# CYV15G0403.net
KiCad netlist of a schematic drawn in Altium Designer
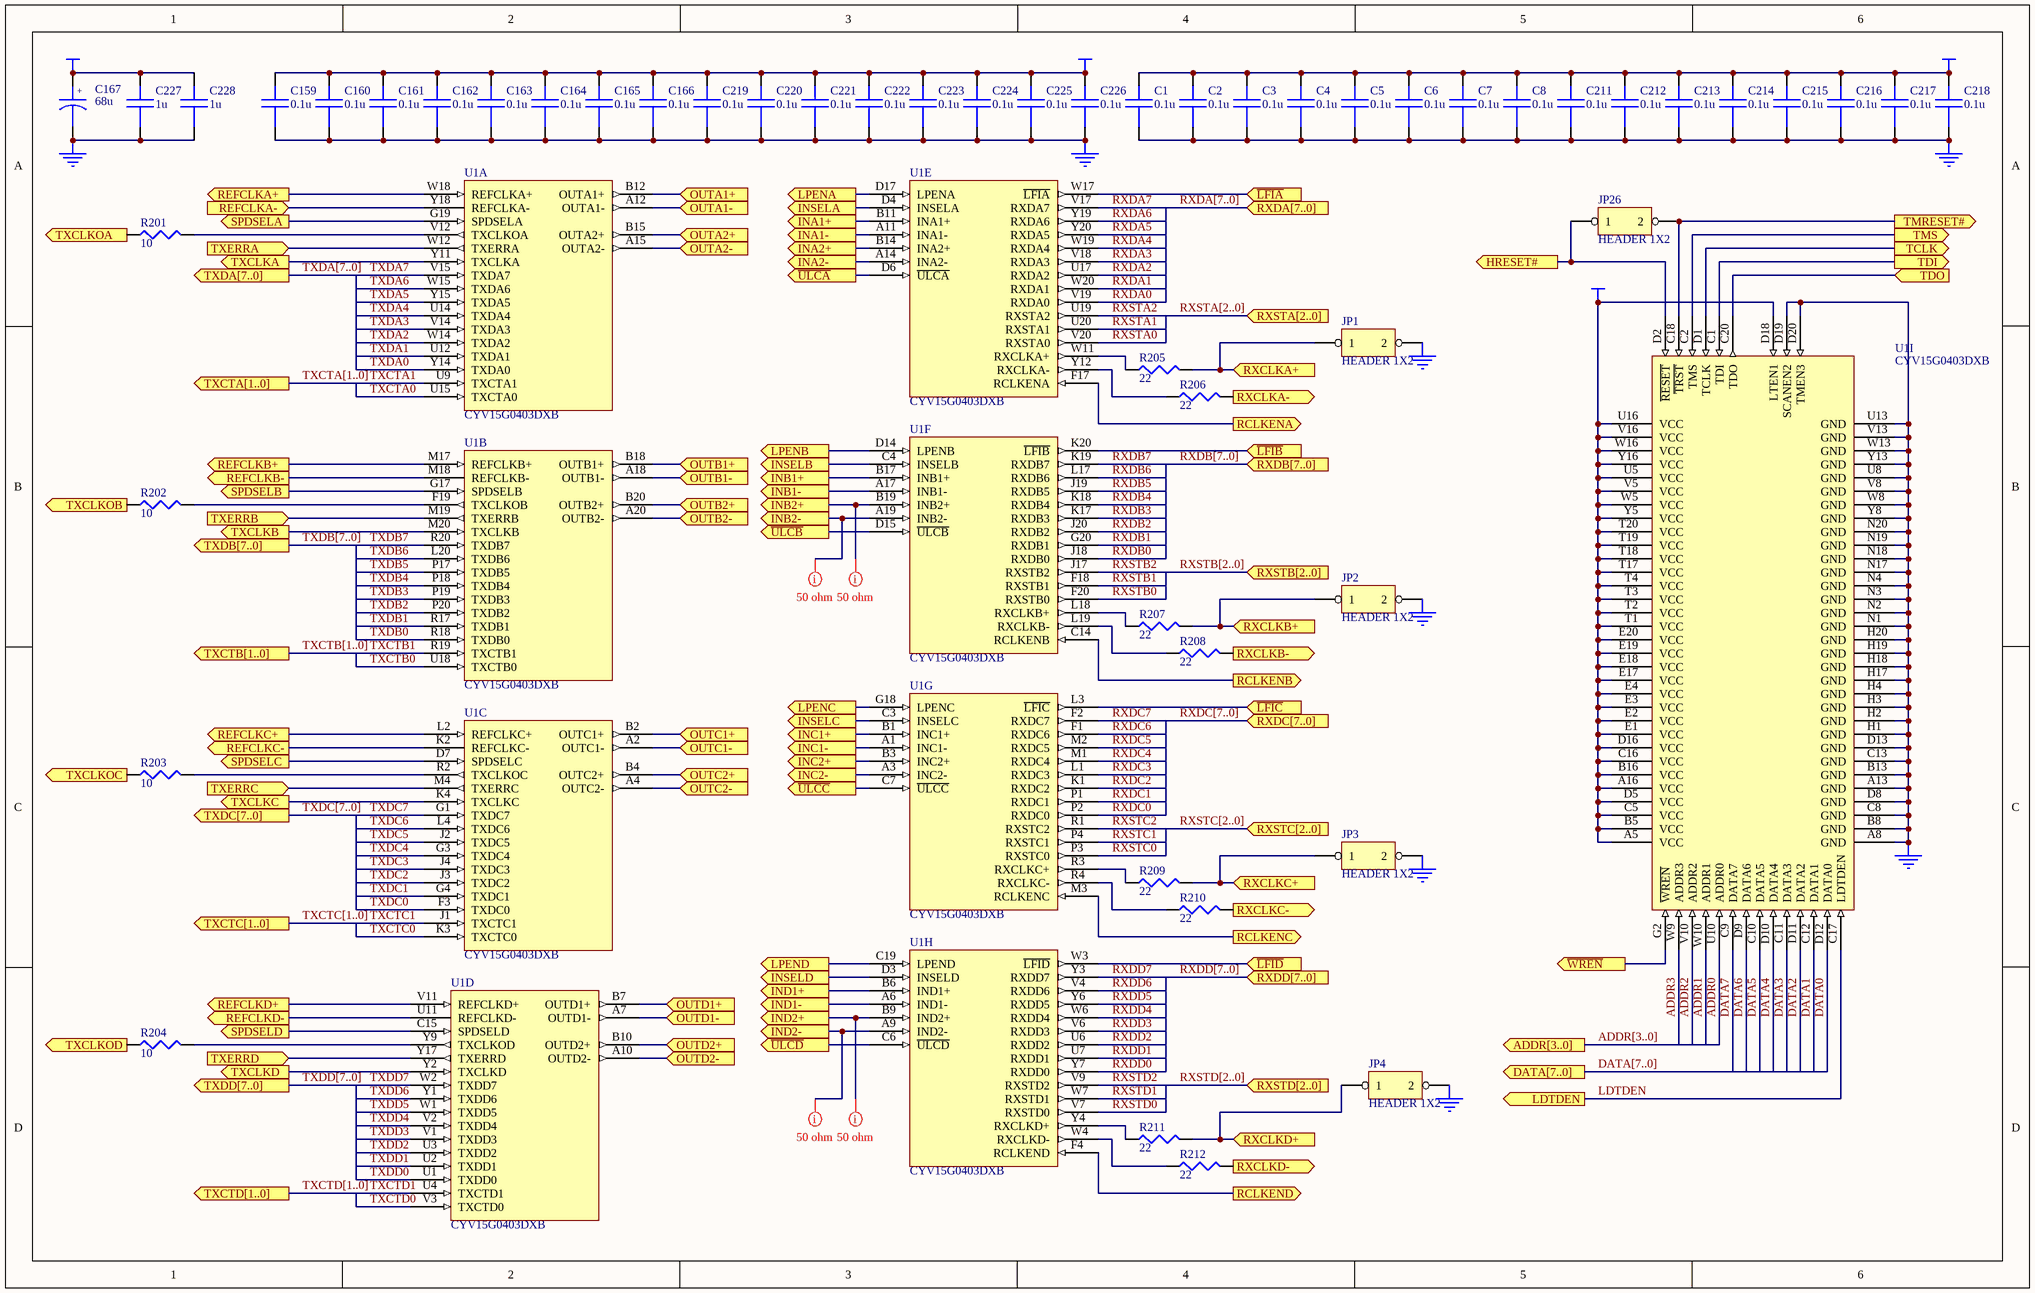
[diagram p0: CYV15G0403.SchDoc]

(export (version "E")
  (design (tool "Eeschema 10.0.6"))
  (components
    (comp (ref "C1")
      (value "~")
      (footprint "0603")
      (description "SMT CAP")
      (libsource (lib "Cypress Molson") (part "CAP"))
    )
    (comp (ref "C2")
      (value "~")
      (footprint "0603")
      (description "SMT CAP")
      (libsource (lib "Cypress Molson") (part "CAP"))
    )
    (comp (ref "C3")
      (value "~")
      (footprint "0603")
      (description "SMT CAP")
      (libsource (lib "Cypress Molson") (part "CAP"))
    )
    (comp (ref "C4")
      (value "~")
      (footprint "0603")
      (description "SMT CAP")
      (libsource (lib "Cypress Molson") (part "CAP"))
    )
    (comp (ref "C5")
      (value "~")
      (footprint "0603")
      (description "SMT CAP")
      (libsource (lib "Cypress Molson") (part "CAP"))
    )
    (comp (ref "C6")
      (value "~")
      (footprint "0603")
      (description "SMT CAP")
      (libsource (lib "Cypress Molson") (part "CAP"))
    )
    (comp (ref "C7")
      (value "~")
      (footprint "0603")
      (description "SMT CAP")
      (libsource (lib "Cypress Molson") (part "CAP"))
    )
    (comp (ref "C8")
      (value "~")
      (footprint "0603")
      (description "SMT CAP")
      (libsource (lib "Cypress Molson") (part "CAP"))
    )
    (comp (ref "C159")
      (value "~")
      (footprint "0603")
      (description "SMT CAP")
      (libsource (lib "Cypress Molson") (part "CAP"))
    )
    (comp (ref "C160")
      (value "~")
      (footprint "0603")
      (description "SMT CAP")
      (libsource (lib "Cypress Molson") (part "CAP"))
    )
    (comp (ref "C161")
      (value "~")
      (footprint "0603")
      (description "SMT CAP")
      (libsource (lib "Cypress Molson") (part "CAP"))
    )
    (comp (ref "C162")
      (value "~")
      (footprint "0603")
      (description "SMT CAP")
      (libsource (lib "Cypress Molson") (part "CAP"))
    )
    (comp (ref "C163")
      (value "~")
      (footprint "0603")
      (description "SMT CAP")
      (libsource (lib "Cypress Molson") (part "CAP"))
    )
    (comp (ref "C164")
      (value "~")
      (footprint "0603")
      (description "SMT CAP")
      (libsource (lib "Cypress Molson") (part "CAP"))
    )
    (comp (ref "C165")
      (value "~")
      (footprint "0603")
      (description "SMT CAP")
      (libsource (lib "Cypress Molson") (part "CAP"))
    )
    (comp (ref "C166")
      (value "~")
      (footprint "0603")
      (description "SMT CAP")
      (libsource (lib "Cypress Molson") (part "CAP"))
    )
    (comp (ref "C167")
      (value "68u")
      (footprint "6032")
      (libsource (lib "Cypress Molson") (part "CAPACITOR POL"))
    )
    (comp (ref "C211")
      (value "~")
      (footprint "0603")
      (description "SMT CAP")
      (libsource (lib "Cypress Molson") (part "CAP"))
    )
    (comp (ref "C212")
      (value "~")
      (footprint "0603")
      (description "SMT CAP")
      (libsource (lib "Cypress Molson") (part "CAP"))
    )
    (comp (ref "C213")
      (value "~")
      (footprint "0603")
      (description "SMT CAP")
      (libsource (lib "Cypress Molson") (part "CAP"))
    )
    (comp (ref "C214")
      (value "~")
      (footprint "0603")
      (description "SMT CAP")
      (libsource (lib "Cypress Molson") (part "CAP"))
    )
    (comp (ref "C215")
      (value "~")
      (footprint "0603")
      (description "SMT CAP")
      (libsource (lib "Cypress Molson") (part "CAP"))
    )
    (comp (ref "C216")
      (value "~")
      (footprint "0603")
      (description "SMT CAP")
      (libsource (lib "Cypress Molson") (part "CAP"))
    )
    (comp (ref "C217")
      (value "~")
      (footprint "0603")
      (description "SMT CAP")
      (libsource (lib "Cypress Molson") (part "CAP"))
    )
    (comp (ref "C218")
      (value "~")
      (footprint "0603")
      (description "SMT CAP")
      (libsource (lib "Cypress Molson") (part "CAP"))
    )
    (comp (ref "C219")
      (value "~")
      (footprint "0603")
      (description "SMT CAP")
      (libsource (lib "Cypress Molson") (part "CAP"))
    )
    (comp (ref "C220")
      (value "~")
      (footprint "0603")
      (description "SMT CAP")
      (libsource (lib "Cypress Molson") (part "CAP"))
    )
    (comp (ref "C221")
      (value "~")
      (footprint "0603")
      (description "SMT CAP")
      (libsource (lib "Cypress Molson") (part "CAP"))
    )
    (comp (ref "C222")
      (value "~")
      (footprint "0603")
      (description "SMT CAP")
      (libsource (lib "Cypress Molson") (part "CAP"))
    )
    (comp (ref "C223")
      (value "~")
      (footprint "0603")
      (description "SMT CAP")
      (libsource (lib "Cypress Molson") (part "CAP"))
    )
    (comp (ref "C224")
      (value "~")
      (footprint "0603")
      (description "SMT CAP")
      (libsource (lib "Cypress Molson") (part "CAP"))
    )
    (comp (ref "C225")
      (value "~")
      (footprint "0603")
      (description "SMT CAP")
      (libsource (lib "Cypress Molson") (part "CAP"))
    )
    (comp (ref "C226")
      (value "~")
      (footprint "0603")
      (description "SMT CAP")
      (libsource (lib "Cypress Molson") (part "CAP"))
    )
    (comp (ref "C227")
      (value "~")
      (footprint "0805")
      (description "SMT CAP")
      (libsource (lib "Cypress Molson") (part "CAP"))
    )
    (comp (ref "C228")
      (value "~")
      (footprint "0805")
      (description "SMT CAP")
      (libsource (lib "Cypress Molson") (part "CAP"))
    )
    (comp (ref "JP1") (value "~") (footprint "1X2PIN") (libsource (lib "Cypress Molson") (part "HEADER 1X2")))
    (comp (ref "JP2") (value "~") (footprint "1X2PIN") (libsource (lib "Cypress Molson") (part "HEADER 1X2")))
    (comp (ref "JP3") (value "~") (footprint "1X2PIN") (libsource (lib "Cypress Molson") (part "HEADER 1X2")))
    (comp (ref "JP4") (value "~") (footprint "1X2PIN") (libsource (lib "Cypress Molson") (part "HEADER 1X2")))
    (comp (ref "JP26")
      (value "~")
      (footprint "1X2PIN")
      (libsource (lib "Cypress Molson") (part "HEADER 1X2"))
    )
    (comp (ref "R201") (value "10") (footprint "0603") (libsource (lib "Cypress Molson") (part "RES1")))
    (comp (ref "R202") (value "10") (footprint "0603") (libsource (lib "Cypress Molson") (part "RES1")))
    (comp (ref "R203") (value "10") (footprint "0603") (libsource (lib "Cypress Molson") (part "RES1")))
    (comp (ref "R204") (value "10") (footprint "0603") (libsource (lib "Cypress Molson") (part "RES1")))
    (comp (ref "R205") (value "22") (footprint "0603") (libsource (lib "Cypress Molson") (part "RES1")))
    (comp (ref "R206") (value "22") (footprint "0603") (libsource (lib "Cypress Molson") (part "RES1")))
    (comp (ref "R207") (value "22") (footprint "0603") (libsource (lib "Cypress Molson") (part "RES1")))
    (comp (ref "R208") (value "22") (footprint "0603") (libsource (lib "Cypress Molson") (part "RES1")))
    (comp (ref "R209") (value "22") (footprint "0603") (libsource (lib "Cypress Molson") (part "RES1")))
    (comp (ref "R210") (value "22") (footprint "0603") (libsource (lib "Cypress Molson") (part "RES1")))
    (comp (ref "R211") (value "22") (footprint "0603") (libsource (lib "Cypress Molson") (part "RES1")))
    (comp (ref "R212") (value "22") (footprint "0603") (libsource (lib "Cypress Molson") (part "RES1")))
    (comp (ref "U1")
      (value "CYV15G0403DXB")
      (footprint "BGA27X27-B256")
      (libsource (lib "") (part "CYV15G0403DXB_1"))
    )
  )
  (nets
    (net (code "1") (name "+3.3V") (class "Default")
      (node (ref "C1") (pin "1") (pinfunction "1_1") (pintype "passive"))
      (node (ref "C159") (pin "1") (pinfunction "1_1") (pintype "passive"))
      (node (ref "C160") (pin "1") (pinfunction "1_1") (pintype "passive"))
      (node (ref "C161") (pin "1") (pinfunction "1_1") (pintype "passive"))
      (node (ref "C162") (pin "1") (pinfunction "1_1") (pintype "passive"))
      (node (ref "C163") (pin "1") (pinfunction "1_1") (pintype "passive"))
      (node (ref "C164") (pin "1") (pinfunction "1_1") (pintype "passive"))
      (node (ref "C165") (pin "1") (pinfunction "1_1") (pintype "passive"))
      (node (ref "C166") (pin "1") (pinfunction "1_1") (pintype "passive"))
      (node (ref "C167") (pin "1") (pinfunction "1_1") (pintype "passive"))
      (node (ref "C2") (pin "1") (pinfunction "1_1") (pintype "passive"))
      (node (ref "C211") (pin "1") (pinfunction "1_1") (pintype "passive"))
      (node (ref "C212") (pin "1") (pinfunction "1_1") (pintype "passive"))
      (node (ref "C213") (pin "1") (pinfunction "1_1") (pintype "passive"))
      (node (ref "C214") (pin "1") (pinfunction "1_1") (pintype "passive"))
      (node (ref "C215") (pin "1") (pinfunction "1_1") (pintype "passive"))
      (node (ref "C216") (pin "1") (pinfunction "1_1") (pintype "passive"))
      (node (ref "C217") (pin "1") (pinfunction "1_1") (pintype "passive"))
      (node (ref "C218") (pin "1") (pinfunction "1_1") (pintype "passive"))
      (node (ref "C219") (pin "1") (pinfunction "1_1") (pintype "passive"))
      (node (ref "C220") (pin "1") (pinfunction "1_1") (pintype "passive"))
      (node (ref "C221") (pin "1") (pinfunction "1_1") (pintype "passive"))
      (node (ref "C222") (pin "1") (pinfunction "1_1") (pintype "passive"))
      (node (ref "C223") (pin "1") (pinfunction "1_1") (pintype "passive"))
      (node (ref "C224") (pin "1") (pinfunction "1_1") (pintype "passive"))
      (node (ref "C225") (pin "1") (pinfunction "1_1") (pintype "passive"))
      (node (ref "C226") (pin "1") (pinfunction "1_1") (pintype "passive"))
      (node (ref "C227") (pin "1") (pinfunction "1_1") (pintype "passive"))
      (node (ref "C228") (pin "1") (pinfunction "1_1") (pintype "passive"))
      (node (ref "C3") (pin "1") (pinfunction "1_1") (pintype "passive"))
      (node (ref "C4") (pin "1") (pinfunction "1_1") (pintype "passive"))
      (node (ref "C5") (pin "1") (pinfunction "1_1") (pintype "passive"))
      (node (ref "C6") (pin "1") (pinfunction "1_1") (pintype "passive"))
      (node (ref "C7") (pin "1") (pinfunction "1_1") (pintype "passive"))
      (node (ref "C8") (pin "1") (pinfunction "1_1") (pintype "passive"))
      (node (ref "U1") (pin "A16") (pinfunction "VCC_A16") (pintype "power_in"))
      (node (ref "U1") (pin "A5") (pinfunction "VCC_A5") (pintype "power_in"))
      (node (ref "U1") (pin "B16") (pinfunction "VCC_B16") (pintype "power_in"))
      (node (ref "U1") (pin "B5") (pinfunction "VCC_B5") (pintype "power_in"))
      (node (ref "U1") (pin "C16") (pinfunction "VCC_C16") (pintype "power_in"))
      (node (ref "U1") (pin "C5") (pinfunction "VCC_C5") (pintype "power_in"))
      (node (ref "U1") (pin "D16") (pinfunction "VCC_D16") (pintype "power_in"))
      (node (ref "U1") (pin "D18") (pinfunction "LTEN1_D18") (pintype "input"))
      (node (ref "U1") (pin "D5") (pinfunction "VCC_D5") (pintype "power_in"))
      (node (ref "U1") (pin "E1") (pinfunction "VCC_E1") (pintype "power_in"))
      (node (ref "U1") (pin "E17") (pinfunction "VCC_E17") (pintype "power_in"))
      (node (ref "U1") (pin "E18") (pinfunction "VCC_E18") (pintype "power_in"))
      (node (ref "U1") (pin "E19") (pinfunction "VCC_E19") (pintype "power_in"))
      (node (ref "U1") (pin "E2") (pinfunction "VCC_E2") (pintype "power_in"))
      (node (ref "U1") (pin "E20") (pinfunction "VCC_E20") (pintype "power_in"))
      (node (ref "U1") (pin "E3") (pinfunction "VCC_E3") (pintype "power_in"))
      (node (ref "U1") (pin "E4") (pinfunction "VCC_E4") (pintype "power_in"))
      (node (ref "U1") (pin "T1") (pinfunction "VCC_T1") (pintype "power_in"))
      (node (ref "U1") (pin "T17") (pinfunction "VCC_T17") (pintype "power_in"))
      (node (ref "U1") (pin "T18") (pinfunction "VCC_T18") (pintype "power_in"))
      (node (ref "U1") (pin "T19") (pinfunction "VCC_T19") (pintype "power_in"))
      (node (ref "U1") (pin "T2") (pinfunction "VCC_T2") (pintype "power_in"))
      (node (ref "U1") (pin "T20") (pinfunction "VCC_T20") (pintype "power_in"))
      (node (ref "U1") (pin "T3") (pinfunction "VCC_T3") (pintype "power_in"))
      (node (ref "U1") (pin "T4") (pinfunction "VCC_T4") (pintype "power_in"))
      (node (ref "U1") (pin "U16") (pinfunction "VCC_U16") (pintype "power_in"))
      (node (ref "U1") (pin "U5") (pinfunction "VCC_U5") (pintype "power_in"))
      (node (ref "U1") (pin "V16") (pinfunction "VCC_V16") (pintype "power_in"))
      (node (ref "U1") (pin "V5") (pinfunction "VCC_V5") (pintype "power_in"))
      (node (ref "U1") (pin "W16") (pinfunction "VCC_W16") (pintype "power_in"))
      (node (ref "U1") (pin "W5") (pinfunction "VCC_W5") (pintype "power_in"))
      (node (ref "U1") (pin "Y16") (pinfunction "VCC_Y16") (pintype "power_in"))
      (node (ref "U1") (pin "Y5") (pinfunction "VCC_Y5") (pintype "power_in"))
    )
    (net (code "2") (name "/ADDR0") (class "Default")
      (node (ref "U1") (pin "U10") (pinfunction "ADDR0_U10") (pintype "input"))
    )
    (net (code "3") (name "/ADDR1") (class "Default")
      (node (ref "U1") (pin "W10") (pinfunction "ADDR1_W10") (pintype "input"))
    )
    (net (code "4") (name "/ADDR2") (class "Default")
      (node (ref "U1") (pin "V10") (pinfunction "ADDR2_V10") (pintype "input"))
    )
    (net (code "5") (name "/ADDR3") (class "Default")
      (node (ref "U1") (pin "W9") (pinfunction "ADDR3_W9") (pintype "input"))
    )
    (net (code "7") (name "/DATA0") (class "Default")
      (node (ref "U1") (pin "D12") (pinfunction "DATA0_D12") (pintype "input"))
    )
    (net (code "8") (name "/DATA1") (class "Default")
      (node (ref "U1") (pin "C12") (pinfunction "DATA1_C12") (pintype "input"))
    )
    (net (code "9") (name "/DATA2") (class "Default")
      (node (ref "U1") (pin "D11") (pinfunction "DATA2_D11") (pintype "input"))
    )
    (net (code "10") (name "/DATA3") (class "Default")
      (node (ref "U1") (pin "C11") (pinfunction "DATA3_C11") (pintype "input"))
    )
    (net (code "11") (name "/DATA4") (class "Default")
      (node (ref "U1") (pin "D10") (pinfunction "DATA4_D10") (pintype "input"))
    )
    (net (code "12") (name "/DATA5") (class "Default")
      (node (ref "U1") (pin "C10") (pinfunction "DATA5_C10") (pintype "input"))
    )
    (net (code "13") (name "/DATA6") (class "Default")
      (node (ref "U1") (pin "D9") (pinfunction "DATA6_D9") (pintype "input"))
    )
    (net (code "14") (name "/DATA7") (class "Default")
      (node (ref "U1") (pin "C9") (pinfunction "DATA7_C9") (pintype "input"))
    )
    (net (code "16") (name "/HRESET#") (class "Default")
      (node (ref "JP26") (pin "1") (pinfunction "1_1") (pintype "passive"))
      (node (ref "U1") (pin "D2") (pinfunction "~{RESET}_D2") (pintype "input"))
    )
    (net (code "17") (name "/INA1+") (class "Default")
      (node (ref "U1") (pin "B11") (pinfunction "INA1+_B11") (pintype "input"))
    )
    (net (code "18") (name "/INA1-") (class "Default")
      (node (ref "U1") (pin "A11") (pinfunction "INA1-_A11") (pintype "input"))
    )
    (net (code "19") (name "/INA2+") (class "Default")
      (node (ref "U1") (pin "B14") (pinfunction "INA2+_B14") (pintype "input"))
    )
    (net (code "20") (name "/INA2-") (class "Default")
      (node (ref "U1") (pin "A14") (pinfunction "INA2-_A14") (pintype "input"))
    )
    (net (code "21") (name "/INB1+") (class "Default")
      (node (ref "U1") (pin "B17") (pinfunction "INB1+_B17") (pintype "input"))
    )
    (net (code "22") (name "/INB1-") (class "Default")
      (node (ref "U1") (pin "A17") (pinfunction "INB1-_A17") (pintype "input"))
    )
    (net (code "23") (name "/INB2+") (class "Default")
      (node (ref "U1") (pin "B19") (pinfunction "INB2+_B19") (pintype "input"))
    )
    (net (code "24") (name "/INB2-") (class "Default")
      (node (ref "U1") (pin "A19") (pinfunction "INB2-_A19") (pintype "input"))
    )
    (net (code "25") (name "/INC1+") (class "Default")
      (node (ref "U1") (pin "B1") (pinfunction "INC1+_B1") (pintype "input"))
    )
    (net (code "26") (name "/INC1-") (class "Default")
      (node (ref "U1") (pin "A1") (pinfunction "INC1-_A1") (pintype "input"))
    )
    (net (code "27") (name "/INC2+") (class "Default")
      (node (ref "U1") (pin "B3") (pinfunction "INC2+_B3") (pintype "input"))
    )
    (net (code "28") (name "/INC2-") (class "Default")
      (node (ref "U1") (pin "A3") (pinfunction "INC2-_A3") (pintype "input"))
    )
    (net (code "29") (name "/IND1+") (class "Default")
      (node (ref "U1") (pin "B6") (pinfunction "IND1+_B6") (pintype "input"))
    )
    (net (code "30") (name "/IND1-") (class "Default")
      (node (ref "U1") (pin "A6") (pinfunction "IND1-_A6") (pintype "input"))
    )
    (net (code "31") (name "/IND2+") (class "Default")
      (node (ref "U1") (pin "B9") (pinfunction "IND2+_B9") (pintype "input"))
    )
    (net (code "32") (name "/IND2-") (class "Default")
      (node (ref "U1") (pin "A9") (pinfunction "IND2-_A9") (pintype "input"))
    )
    (net (code "33") (name "/INSELA") (class "Default")
      (node (ref "U1") (pin "D4") (pinfunction "INSELA_D4") (pintype "input"))
    )
    (net (code "34") (name "/INSELB") (class "Default")
      (node (ref "U1") (pin "C4") (pinfunction "INSELB_C4") (pintype "input"))
    )
    (net (code "35") (name "/INSELC") (class "Default")
      (node (ref "U1") (pin "C3") (pinfunction "INSELC_C3") (pintype "input"))
    )
    (net (code "36") (name "/INSELD") (class "Default")
      (node (ref "U1") (pin "D3") (pinfunction "INSELD_D3") (pintype "input"))
    )
    (net (code "37") (name "/LDTDEN") (class "Default")
      (node (ref "U1") (pin "C17") (pinfunction "LDTDEN_C17") (pintype "input"))
    )
    (net (code "38") (name "/LPENA") (class "Default")
      (node (ref "U1") (pin "D17") (pinfunction "LPENA_D17") (pintype "input"))
    )
    (net (code "39") (name "/LPENB") (class "Default")
      (node (ref "U1") (pin "D14") (pinfunction "LPENB_D14") (pintype "input"))
    )
    (net (code "40") (name "/LPENC") (class "Default")
      (node (ref "U1") (pin "G18") (pinfunction "LPENC_G18") (pintype "input"))
    )
    (net (code "41") (name "/LPEND") (class "Default")
      (node (ref "U1") (pin "C19") (pinfunction "LPEND_C19") (pintype "input"))
    )
    (net (code "42") (name "/OUTA1+") (class "Default")
      (node (ref "U1") (pin "B12") (pinfunction "OUTA1+_B12") (pintype "output"))
    )
    (net (code "43") (name "/OUTA1-") (class "Default")
      (node (ref "U1") (pin "A12") (pinfunction "OUTA1-_A12") (pintype "output"))
    )
    (net (code "44") (name "/OUTA2+") (class "Default")
      (node (ref "U1") (pin "B15") (pinfunction "OUTA2+_B15") (pintype "output"))
    )
    (net (code "45") (name "/OUTA2-") (class "Default")
      (node (ref "U1") (pin "A15") (pinfunction "OUTA2-_A15") (pintype "output"))
    )
    (net (code "46") (name "/OUTB1+") (class "Default")
      (node (ref "U1") (pin "B18") (pinfunction "OUTB1+_B18") (pintype "output"))
    )
    (net (code "47") (name "/OUTB1-") (class "Default")
      (node (ref "U1") (pin "A18") (pinfunction "OUTB1-_A18") (pintype "output"))
    )
    (net (code "48") (name "/OUTB2+") (class "Default")
      (node (ref "U1") (pin "B20") (pinfunction "OUTB2+_B20") (pintype "output"))
    )
    (net (code "49") (name "/OUTB2-") (class "Default")
      (node (ref "U1") (pin "A20") (pinfunction "OUTB2-_A20") (pintype "output"))
    )
    (net (code "50") (name "/OUTC1+") (class "Default")
      (node (ref "U1") (pin "B2") (pinfunction "OUTC1+_B2") (pintype "output"))
    )
    (net (code "51") (name "/OUTC1-") (class "Default")
      (node (ref "U1") (pin "A2") (pinfunction "OUTC1-_A2") (pintype "output"))
    )
    (net (code "52") (name "/OUTC2+") (class "Default")
      (node (ref "U1") (pin "B4") (pinfunction "OUTC2+_B4") (pintype "output"))
    )
    (net (code "53") (name "/OUTC2-") (class "Default")
      (node (ref "U1") (pin "A4") (pinfunction "OUTC2-_A4") (pintype "output"))
    )
    (net (code "54") (name "/OUTD1+") (class "Default")
      (node (ref "U1") (pin "B7") (pinfunction "OUTD1+_B7") (pintype "output"))
    )
    (net (code "55") (name "/OUTD1-") (class "Default")
      (node (ref "U1") (pin "A7") (pinfunction "OUTD1-_A7") (pintype "output"))
    )
    (net (code "56") (name "/OUTD2+") (class "Default")
      (node (ref "U1") (pin "B10") (pinfunction "OUTD2+_B10") (pintype "output"))
    )
    (net (code "57") (name "/OUTD2-") (class "Default")
      (node (ref "U1") (pin "A10") (pinfunction "OUTD2-_A10") (pintype "output"))
    )
    (net (code "58") (name "/RCLKENA") (class "Default")
      (node (ref "U1") (pin "F17") (pinfunction "RCLKENA_F17") (pintype "input"))
    )
    (net (code "59") (name "/RCLKENB") (class "Default")
      (node (ref "U1") (pin "C14") (pinfunction "RCLKENB_C14") (pintype "input"))
    )
    (net (code "60") (name "/RCLKENC") (class "Default")
      (node (ref "U1") (pin "M3") (pinfunction "RCLKENC_M3") (pintype "input"))
    )
    (net (code "61") (name "/RCLKEND") (class "Default")
      (node (ref "U1") (pin "F4") (pinfunction "RCLKEND_F4") (pintype "input"))
    )
    (net (code "62") (name "/REFCLKA+") (class "Default")
      (node (ref "U1") (pin "W18") (pinfunction "REFCLKA+_W18") (pintype "input"))
    )
    (net (code "63") (name "/REFCLKA-") (class "Default")
      (node (ref "U1") (pin "Y18") (pinfunction "REFCLKA-_Y18") (pintype "passive"))
    )
    (net (code "64") (name "/REFCLKB+") (class "Default")
      (node (ref "U1") (pin "M17") (pinfunction "REFCLKB+_M17") (pintype "input"))
    )
    (net (code "65") (name "/REFCLKB-") (class "Default")
      (node (ref "U1") (pin "M18") (pinfunction "REFCLKB-_M18") (pintype "passive"))
    )
    (net (code "66") (name "/REFCLKC+") (class "Default")
      (node (ref "U1") (pin "L2") (pinfunction "REFCLKC+_L2") (pintype "input"))
    )
    (net (code "67") (name "/REFCLKC-") (class "Default")
      (node (ref "U1") (pin "K2") (pinfunction "REFCLKC-_K2") (pintype "passive"))
    )
    (net (code "68") (name "/REFCLKD+") (class "Default")
      (node (ref "U1") (pin "V11") (pinfunction "REFCLKD+_V11") (pintype "input"))
    )
    (net (code "69") (name "/REFCLKD-") (class "Default")
      (node (ref "U1") (pin "U11") (pinfunction "REFCLKD-_U11") (pintype "passive"))
    )
    (net (code "70") (name "/RXCLKA+") (class "Default")
      (node (ref "JP1") (pin "1") (pinfunction "1_1") (pintype "passive"))
      (node (ref "R205") (pin "2") (pintype "passive"))
    )
    (net (code "71") (name "/RXCLKA-") (class "Default") (node (ref "R206") (pin "2") (pintype "passive")))
    (net (code "72") (name "/RXCLKB+") (class "Default")
      (node (ref "JP2") (pin "1") (pinfunction "1_1") (pintype "passive"))
      (node (ref "R207") (pin "2") (pintype "passive"))
    )
    (net (code "73") (name "/RXCLKB-") (class "Default") (node (ref "R208") (pin "2") (pintype "passive")))
    (net (code "74") (name "/RXCLKC+") (class "Default")
      (node (ref "JP3") (pin "1") (pinfunction "1_1") (pintype "passive"))
      (node (ref "R209") (pin "2") (pintype "passive"))
    )
    (net (code "75") (name "/RXCLKC-") (class "Default") (node (ref "R210") (pin "2") (pintype "passive")))
    (net (code "76") (name "/RXCLKD+") (class "Default")
      (node (ref "JP4") (pin "1") (pinfunction "1_1") (pintype "passive"))
      (node (ref "R211") (pin "2") (pintype "passive"))
    )
    (net (code "77") (name "/RXCLKD-") (class "Default") (node (ref "R212") (pin "2") (pintype "passive")))
    (net (code "78") (name "/RXDA0") (class "Default")
      (node (ref "U1") (pin "V19") (pinfunction "RXDA0_V19") (pintype "output"))
    )
    (net (code "79") (name "/RXDA1") (class "Default")
      (node (ref "U1") (pin "W20") (pinfunction "RXDA1_W20") (pintype "output"))
    )
    (net (code "80") (name "/RXDA2") (class "Default")
      (node (ref "U1") (pin "U17") (pinfunction "RXDA2_U17") (pintype "output"))
    )
    (net (code "81") (name "/RXDA3") (class "Default")
      (node (ref "U1") (pin "V18") (pinfunction "RXDA3_V18") (pintype "output"))
    )
    (net (code "82") (name "/RXDA4") (class "Default")
      (node (ref "U1") (pin "W19") (pinfunction "RXDA4_W19") (pintype "output"))
    )
    (net (code "83") (name "/RXDA5") (class "Default")
      (node (ref "U1") (pin "Y20") (pinfunction "RXDA5_Y20") (pintype "output"))
    )
    (net (code "84") (name "/RXDA6") (class "Default")
      (node (ref "U1") (pin "Y19") (pinfunction "RXDA6_Y19") (pintype "output"))
    )
    (net (code "85") (name "/RXDA7") (class "Default")
      (node (ref "U1") (pin "V17") (pinfunction "RXDA7_V17") (pintype "output"))
    )
    (net (code "87") (name "/RXDB0") (class "Default")
      (node (ref "U1") (pin "J18") (pinfunction "RXDB0_J18") (pintype "output"))
    )
    (net (code "88") (name "/RXDB1") (class "Default")
      (node (ref "U1") (pin "G20") (pinfunction "RXDB1_G20") (pintype "output"))
    )
    (net (code "89") (name "/RXDB2") (class "Default")
      (node (ref "U1") (pin "J20") (pinfunction "RXDB2_J20") (pintype "output"))
    )
    (net (code "90") (name "/RXDB3") (class "Default")
      (node (ref "U1") (pin "K17") (pinfunction "RXDB3_K17") (pintype "output"))
    )
    (net (code "91") (name "/RXDB4") (class "Default")
      (node (ref "U1") (pin "K18") (pinfunction "RXDB4_K18") (pintype "output"))
    )
    (net (code "92") (name "/RXDB5") (class "Default")
      (node (ref "U1") (pin "J19") (pinfunction "RXDB5_J19") (pintype "output"))
    )
    (net (code "93") (name "/RXDB6") (class "Default")
      (node (ref "U1") (pin "L17") (pinfunction "RXDB6_L17") (pintype "output"))
    )
    (net (code "94") (name "/RXDB7") (class "Default")
      (node (ref "U1") (pin "K19") (pinfunction "RXDB7_K19") (pintype "output"))
    )
    (net (code "96") (name "/RXDC0") (class "Default")
      (node (ref "U1") (pin "P2") (pinfunction "RXDC0_P2") (pintype "output"))
    )
    (net (code "97") (name "/RXDC1") (class "Default")
      (node (ref "U1") (pin "P1") (pinfunction "RXDC1_P1") (pintype "output"))
    )
    (net (code "98") (name "/RXDC2") (class "Default")
      (node (ref "U1") (pin "K1") (pinfunction "RXDC2_K1") (pintype "output"))
    )
    (net (code "99") (name "/RXDC3") (class "Default")
      (node (ref "U1") (pin "L1") (pinfunction "RXDC3_L1") (pintype "output"))
    )
    (net (code "100") (name "/RXDC4") (class "Default")
      (node (ref "U1") (pin "M1") (pinfunction "RXDC4_M1") (pintype "output"))
    )
    (net (code "101") (name "/RXDC5") (class "Default")
      (node (ref "U1") (pin "M2") (pinfunction "RXDC5_M2") (pintype "output"))
    )
    (net (code "102") (name "/RXDC6") (class "Default")
      (node (ref "U1") (pin "F1") (pinfunction "RXDC6_F1") (pintype "output"))
    )
    (net (code "103") (name "/RXDC7") (class "Default")
      (node (ref "U1") (pin "F2") (pinfunction "RXDC7_F2") (pintype "output"))
    )
    (net (code "105") (name "/RXDD0") (class "Default")
      (node (ref "U1") (pin "Y7") (pinfunction "RXDD0_Y7") (pintype "output"))
    )
    (net (code "106") (name "/RXDD1") (class "Default")
      (node (ref "U1") (pin "U7") (pinfunction "RXDD1_U7") (pintype "output"))
    )
    (net (code "107") (name "/RXDD2") (class "Default")
      (node (ref "U1") (pin "U6") (pinfunction "RXDD2_U6") (pintype "output"))
    )
    (net (code "108") (name "/RXDD3") (class "Default")
      (node (ref "U1") (pin "V6") (pinfunction "RXDD3_V6") (pintype "output"))
    )
    (net (code "109") (name "/RXDD4") (class "Default")
      (node (ref "U1") (pin "W6") (pinfunction "RXDD4_W6") (pintype "output"))
    )
    (net (code "110") (name "/RXDD5") (class "Default")
      (node (ref "U1") (pin "Y6") (pinfunction "RXDD5_Y6") (pintype "output"))
    )
    (net (code "111") (name "/RXDD6") (class "Default")
      (node (ref "U1") (pin "V4") (pinfunction "RXDD6_V4") (pintype "output"))
    )
    (net (code "112") (name "/RXDD7") (class "Default")
      (node (ref "U1") (pin "Y3") (pinfunction "RXDD7_Y3") (pintype "output"))
    )
    (net (code "114") (name "/RXSTA0") (class "Default")
      (node (ref "U1") (pin "V20") (pinfunction "RXSTA0_V20") (pintype "output"))
    )
    (net (code "115") (name "/RXSTA1") (class "Default")
      (node (ref "U1") (pin "U20") (pinfunction "RXSTA1_U20") (pintype "output"))
    )
    (net (code "116") (name "/RXSTA2") (class "Default")
      (node (ref "U1") (pin "U19") (pinfunction "RXSTA2_U19") (pintype "output"))
    )
    (net (code "118") (name "/RXSTB0") (class "Default")
      (node (ref "U1") (pin "F20") (pinfunction "RXSTB0_F20") (pintype "output"))
    )
    (net (code "119") (name "/RXSTB1") (class "Default")
      (node (ref "U1") (pin "F18") (pinfunction "RXSTB1_F18") (pintype "output"))
    )
    (net (code "120") (name "/RXSTB2") (class "Default")
      (node (ref "U1") (pin "J17") (pinfunction "RXSTB2_J17") (pintype "output"))
    )
    (net (code "122") (name "/RXSTC0") (class "Default")
      (node (ref "U1") (pin "P3") (pinfunction "RXSTC0_P3") (pintype "output"))
    )
    (net (code "123") (name "/RXSTC1") (class "Default")
      (node (ref "U1") (pin "P4") (pinfunction "RXSTC1_P4") (pintype "output"))
    )
    (net (code "124") (name "/RXSTC2") (class "Default")
      (node (ref "U1") (pin "R1") (pinfunction "RXSTC2_R1") (pintype "output"))
    )
    (net (code "126") (name "/RXSTD0") (class "Default")
      (node (ref "U1") (pin "V7") (pinfunction "RXSTD0_V7") (pintype "output"))
    )
    (net (code "127") (name "/RXSTD1") (class "Default")
      (node (ref "U1") (pin "W7") (pinfunction "RXSTD1_W7") (pintype "output"))
    )
    (net (code "128") (name "/RXSTD2") (class "Default")
      (node (ref "U1") (pin "V9") (pinfunction "RXSTD2_V9") (pintype "output"))
    )
    (net (code "130") (name "/SPDSELA") (class "Default")
      (node (ref "U1") (pin "G19") (pinfunction "SPDSELA_G19") (pintype "input"))
    )
    (net (code "131") (name "/SPDSELB") (class "Default")
      (node (ref "U1") (pin "G17") (pinfunction "SPDSELB_G17") (pintype "input"))
    )
    (net (code "132") (name "/SPDSELC") (class "Default")
      (node (ref "U1") (pin "D7") (pinfunction "SPDSELC_D7") (pintype "input"))
    )
    (net (code "133") (name "/SPDSELD") (class "Default")
      (node (ref "U1") (pin "C15") (pinfunction "SPDSELD_C15") (pintype "input"))
    )
    (net (code "134") (name "/TCLK") (class "Default")
      (node (ref "U1") (pin "D1") (pinfunction "TCLK_D1") (pintype "input"))
    )
    (net (code "135") (name "/TDI") (class "Default")
      (node (ref "U1") (pin "C1") (pinfunction "TDI_C1") (pintype "input"))
    )
    (net (code "136") (name "/TDO") (class "Default")
      (node (ref "U1") (pin "C20") (pinfunction "TDO_C20") (pintype "output"))
    )
    (net (code "137") (name "/TMRESET#") (class "Default")
      (node (ref "JP26") (pin "2") (pinfunction "2_2") (pintype "passive"))
      (node (ref "U1") (pin "C18") (pinfunction "~{TRST}_C18") (pintype "input"))
    )
    (net (code "138") (name "/TMS") (class "Default")
      (node (ref "U1") (pin "C2") (pinfunction "TMS_C2") (pintype "input"))
    )
    (net (code "139") (name "/TXCLKA") (class "Default")
      (node (ref "U1") (pin "Y11") (pinfunction "TXCLKA_Y11") (pintype "input"))
    )
    (net (code "140") (name "/TXCLKB") (class "Default")
      (node (ref "U1") (pin "M20") (pinfunction "TXCLKB_M20") (pintype "input"))
    )
    (net (code "141") (name "/TXCLKC") (class "Default")
      (node (ref "U1") (pin "K4") (pinfunction "TXCLKC_K4") (pintype "input"))
    )
    (net (code "142") (name "/TXCLKD") (class "Default")
      (node (ref "U1") (pin "Y2") (pinfunction "TXCLKD_Y2") (pintype "input"))
    )
    (net (code "143") (name "/TXCLKOA") (class "Default") (node (ref "R201") (pin "1") (pintype "passive")))
    (net (code "144") (name "/TXCLKOB") (class "Default") (node (ref "R202") (pin "1") (pintype "passive")))
    (net (code "145") (name "/TXCLKOC") (class "Default") (node (ref "R203") (pin "1") (pintype "passive")))
    (net (code "146") (name "/TXCLKOD") (class "Default") (node (ref "R204") (pin "1") (pintype "passive")))
    (net (code "147") (name "/TXCTA0") (class "Default")
      (node (ref "U1") (pin "U15") (pinfunction "TXCTA0_U15") (pintype "input"))
    )
    (net (code "148") (name "/TXCTA1") (class "Default")
      (node (ref "U1") (pin "U9") (pinfunction "TXCTA1_U9") (pintype "input"))
    )
    (net (code "150") (name "/TXCTB0") (class "Default")
      (node (ref "U1") (pin "U18") (pinfunction "TXCTB0_U18") (pintype "input"))
    )
    (net (code "151") (name "/TXCTB1") (class "Default")
      (node (ref "U1") (pin "R19") (pinfunction "TXCTB1_R19") (pintype "input"))
    )
    (net (code "153") (name "/TXCTC0") (class "Default")
      (node (ref "U1") (pin "K3") (pinfunction "TXCTC0_K3") (pintype "input"))
    )
    (net (code "154") (name "/TXCTC1") (class "Default")
      (node (ref "U1") (pin "J1") (pinfunction "TXCTC1_J1") (pintype "input"))
    )
    (net (code "156") (name "/TXCTD0") (class "Default")
      (node (ref "U1") (pin "V3") (pinfunction "TXCTD0_V3") (pintype "input"))
    )
    (net (code "157") (name "/TXCTD1") (class "Default")
      (node (ref "U1") (pin "U4") (pinfunction "TXCTD1_U4") (pintype "input"))
    )
    (net (code "159") (name "/TXDA0") (class "Default")
      (node (ref "U1") (pin "Y14") (pinfunction "TXDA0_Y14") (pintype "input"))
    )
    (net (code "160") (name "/TXDA1") (class "Default")
      (node (ref "U1") (pin "U12") (pinfunction "TXDA1_U12") (pintype "input"))
    )
    (net (code "161") (name "/TXDA2") (class "Default")
      (node (ref "U1") (pin "W14") (pinfunction "TXDA2_W14") (pintype "input"))
    )
    (net (code "162") (name "/TXDA3") (class "Default")
      (node (ref "U1") (pin "V14") (pinfunction "TXDA3_V14") (pintype "input"))
    )
    (net (code "163") (name "/TXDA4") (class "Default")
      (node (ref "U1") (pin "U14") (pinfunction "TXDA4_U14") (pintype "input"))
    )
    (net (code "164") (name "/TXDA5") (class "Default")
      (node (ref "U1") (pin "Y15") (pinfunction "TXDA5_Y15") (pintype "input"))
    )
    (net (code "165") (name "/TXDA6") (class "Default")
      (node (ref "U1") (pin "W15") (pinfunction "TXDA6_W15") (pintype "input"))
    )
    (net (code "166") (name "/TXDA7") (class "Default")
      (node (ref "U1") (pin "V15") (pinfunction "TXDA7_V15") (pintype "input"))
    )
    (net (code "168") (name "/TXDB0") (class "Default")
      (node (ref "U1") (pin "R18") (pinfunction "TXDB0_R18") (pintype "input"))
    )
    (net (code "169") (name "/TXDB1") (class "Default")
      (node (ref "U1") (pin "R17") (pinfunction "TXDB1_R17") (pintype "input"))
    )
    (net (code "170") (name "/TXDB2") (class "Default")
      (node (ref "U1") (pin "P20") (pinfunction "TXDB2_P20") (pintype "input"))
    )
    (net (code "171") (name "/TXDB3") (class "Default")
      (node (ref "U1") (pin "P19") (pinfunction "TXDB3_P19") (pintype "input"))
    )
    (net (code "172") (name "/TXDB4") (class "Default")
      (node (ref "U1") (pin "P18") (pinfunction "TXDB4_P18") (pintype "input"))
    )
    (net (code "173") (name "/TXDB5") (class "Default")
      (node (ref "U1") (pin "P17") (pinfunction "TXDB5_P17") (pintype "input"))
    )
    (net (code "174") (name "/TXDB6") (class "Default")
      (node (ref "U1") (pin "L20") (pinfunction "TXDB6_L20") (pintype "input"))
    )
    (net (code "175") (name "/TXDB7") (class "Default")
      (node (ref "U1") (pin "R20") (pinfunction "TXDB7_R20") (pintype "input"))
    )
    (net (code "177") (name "/TXDC0") (class "Default")
      (node (ref "U1") (pin "F3") (pinfunction "TXDC0_F3") (pintype "input"))
    )
    (net (code "178") (name "/TXDC1") (class "Default")
      (node (ref "U1") (pin "G4") (pinfunction "TXDC1_G4") (pintype "input"))
    )
    (net (code "179") (name "/TXDC2") (class "Default")
      (node (ref "U1") (pin "J3") (pinfunction "TXDC2_J3") (pintype "input"))
    )
    (net (code "180") (name "/TXDC3") (class "Default")
      (node (ref "U1") (pin "J4") (pinfunction "TXDC3_J4") (pintype "input"))
    )
    (net (code "181") (name "/TXDC4") (class "Default")
      (node (ref "U1") (pin "G3") (pinfunction "TXDC4_G3") (pintype "input"))
    )
    (net (code "182") (name "/TXDC5") (class "Default")
      (node (ref "U1") (pin "J2") (pinfunction "TXDC5_J2") (pintype "input"))
    )
    (net (code "183") (name "/TXDC6") (class "Default")
      (node (ref "U1") (pin "L4") (pinfunction "TXDC6_L4") (pintype "input"))
    )
    (net (code "184") (name "/TXDC7") (class "Default")
      (node (ref "U1") (pin "G1") (pinfunction "TXDC7_G1") (pintype "input"))
    )
    (net (code "186") (name "/TXDD0") (class "Default")
      (node (ref "U1") (pin "U1") (pinfunction "TXDD0_U1") (pintype "input"))
    )
    (net (code "187") (name "/TXDD1") (class "Default")
      (node (ref "U1") (pin "U2") (pinfunction "TXDD1_U2") (pintype "input"))
    )
    (net (code "188") (name "/TXDD2") (class "Default")
      (node (ref "U1") (pin "U3") (pinfunction "TXDD2_U3") (pintype "input"))
    )
    (net (code "189") (name "/TXDD3") (class "Default")
      (node (ref "U1") (pin "V1") (pinfunction "TXDD3_V1") (pintype "input"))
    )
    (net (code "190") (name "/TXDD4") (class "Default")
      (node (ref "U1") (pin "V2") (pinfunction "TXDD4_V2") (pintype "input"))
    )
    (net (code "191") (name "/TXDD5") (class "Default")
      (node (ref "U1") (pin "W1") (pinfunction "TXDD5_W1") (pintype "input"))
    )
    (net (code "192") (name "/TXDD6") (class "Default")
      (node (ref "U1") (pin "Y1") (pinfunction "TXDD6_Y1") (pintype "input"))
    )
    (net (code "193") (name "/TXDD7") (class "Default")
      (node (ref "U1") (pin "W2") (pinfunction "TXDD7_W2") (pintype "input"))
    )
    (net (code "195") (name "/TXERRA") (class "Default")
      (node (ref "U1") (pin "W12") (pinfunction "TXERRA_W12") (pintype "output"))
    )
    (net (code "196") (name "/TXERRB") (class "Default")
      (node (ref "U1") (pin "M19") (pinfunction "TXERRB_M19") (pintype "output"))
    )
    (net (code "197") (name "/TXERRC") (class "Default")
      (node (ref "U1") (pin "M4") (pinfunction "TXERRC_M4") (pintype "output"))
    )
    (net (code "198") (name "/TXERRD") (class "Default")
      (node (ref "U1") (pin "Y17") (pinfunction "TXERRD_Y17") (pintype "output"))
    )
    (net (code "199") (name "/~{LFIA}") (class "Default")
      (node (ref "U1") (pin "W17") (pinfunction "~{LFIA}_W17") (pintype "output"))
    )
    (net (code "200") (name "/~{LFIB}") (class "Default")
      (node (ref "U1") (pin "K20") (pinfunction "~{LFIB}_K20") (pintype "output"))
    )
    (net (code "201") (name "/~{LFIC}") (class "Default")
      (node (ref "U1") (pin "L3") (pinfunction "~{LFIC}_L3") (pintype "output"))
    )
    (net (code "202") (name "/~{LFID}") (class "Default")
      (node (ref "U1") (pin "W3") (pinfunction "~{LFID}_W3") (pintype "output"))
    )
    (net (code "203") (name "/~{ULCA}") (class "Default")
      (node (ref "U1") (pin "D6") (pinfunction "~{ULCA}_D6") (pintype "input"))
    )
    (net (code "204") (name "/~{ULCB}") (class "Default")
      (node (ref "U1") (pin "D15") (pinfunction "~{ULCB}_D15") (pintype "input"))
    )
    (net (code "205") (name "/~{ULCC}") (class "Default")
      (node (ref "U1") (pin "C7") (pinfunction "~{ULCC}_C7") (pintype "input"))
    )
    (net (code "206") (name "/~{ULCD}") (class "Default")
      (node (ref "U1") (pin "C6") (pinfunction "~{ULCD}_C6") (pintype "input"))
    )
    (net (code "207") (name "/~{WREN}") (class "Default")
      (node (ref "U1") (pin "G2") (pinfunction "~{WREN}_G2") (pintype "input"))
    )
    (net (code "208") (name "GND") (class "Default")
      (node (ref "C1") (pin "2") (pinfunction "2_2") (pintype "passive"))
      (node (ref "C159") (pin "2") (pinfunction "2_2") (pintype "passive"))
      (node (ref "C160") (pin "2") (pinfunction "2_2") (pintype "passive"))
      (node (ref "C161") (pin "2") (pinfunction "2_2") (pintype "passive"))
      (node (ref "C162") (pin "2") (pinfunction "2_2") (pintype "passive"))
      (node (ref "C163") (pin "2") (pinfunction "2_2") (pintype "passive"))
      (node (ref "C164") (pin "2") (pinfunction "2_2") (pintype "passive"))
      (node (ref "C165") (pin "2") (pinfunction "2_2") (pintype "passive"))
      (node (ref "C166") (pin "2") (pinfunction "2_2") (pintype "passive"))
      (node (ref "C167") (pin "2") (pinfunction "2_2") (pintype "passive"))
      (node (ref "C2") (pin "2") (pinfunction "2_2") (pintype "passive"))
      (node (ref "C211") (pin "2") (pinfunction "2_2") (pintype "passive"))
      (node (ref "C212") (pin "2") (pinfunction "2_2") (pintype "passive"))
      (node (ref "C213") (pin "2") (pinfunction "2_2") (pintype "passive"))
      (node (ref "C214") (pin "2") (pinfunction "2_2") (pintype "passive"))
      (node (ref "C215") (pin "2") (pinfunction "2_2") (pintype "passive"))
      (node (ref "C216") (pin "2") (pinfunction "2_2") (pintype "passive"))
      (node (ref "C217") (pin "2") (pinfunction "2_2") (pintype "passive"))
      (node (ref "C218") (pin "2") (pinfunction "2_2") (pintype "passive"))
      (node (ref "C219") (pin "2") (pinfunction "2_2") (pintype "passive"))
      (node (ref "C220") (pin "2") (pinfunction "2_2") (pintype "passive"))
      (node (ref "C221") (pin "2") (pinfunction "2_2") (pintype "passive"))
      (node (ref "C222") (pin "2") (pinfunction "2_2") (pintype "passive"))
      (node (ref "C223") (pin "2") (pinfunction "2_2") (pintype "passive"))
      (node (ref "C224") (pin "2") (pinfunction "2_2") (pintype "passive"))
      (node (ref "C225") (pin "2") (pinfunction "2_2") (pintype "passive"))
      (node (ref "C226") (pin "2") (pinfunction "2_2") (pintype "passive"))
      (node (ref "C227") (pin "2") (pinfunction "2_2") (pintype "passive"))
      (node (ref "C228") (pin "2") (pinfunction "2_2") (pintype "passive"))
      (node (ref "C3") (pin "2") (pinfunction "2_2") (pintype "passive"))
      (node (ref "C4") (pin "2") (pinfunction "2_2") (pintype "passive"))
      (node (ref "C5") (pin "2") (pinfunction "2_2") (pintype "passive"))
      (node (ref "C6") (pin "2") (pinfunction "2_2") (pintype "passive"))
      (node (ref "C7") (pin "2") (pinfunction "2_2") (pintype "passive"))
      (node (ref "C8") (pin "2") (pinfunction "2_2") (pintype "passive"))
      (node (ref "JP1") (pin "2") (pinfunction "2_2") (pintype "passive"))
      (node (ref "JP2") (pin "2") (pinfunction "2_2") (pintype "passive"))
      (node (ref "JP3") (pin "2") (pinfunction "2_2") (pintype "passive"))
      (node (ref "JP4") (pin "2") (pinfunction "2_2") (pintype "passive"))
      (node (ref "U1") (pin "A13") (pinfunction "GND_A13") (pintype "power_in"))
      (node (ref "U1") (pin "A8") (pinfunction "GND_A8") (pintype "power_in"))
      (node (ref "U1") (pin "B13") (pinfunction "GND_B13") (pintype "power_in"))
      (node (ref "U1") (pin "B8") (pinfunction "GND_B8") (pintype "power_in"))
      (node (ref "U1") (pin "C13") (pinfunction "GND_C13") (pintype "power_in"))
      (node (ref "U1") (pin "C8") (pinfunction "GND_C8") (pintype "power_in"))
      (node (ref "U1") (pin "D13") (pinfunction "GND_D13") (pintype "power_in"))
      (node (ref "U1") (pin "D19") (pinfunction "SCANEN2_D19") (pintype "input"))
      (node (ref "U1") (pin "D20") (pinfunction "TMEN3_D20") (pintype "input"))
      (node (ref "U1") (pin "D8") (pinfunction "GND_D8") (pintype "power_in"))
      (node (ref "U1") (pin "H1") (pinfunction "GND_H1") (pintype "power_in"))
      (node (ref "U1") (pin "H17") (pinfunction "GND_H17") (pintype "power_in"))
      (node (ref "U1") (pin "H18") (pinfunction "GND_H18") (pintype "power_in"))
      (node (ref "U1") (pin "H19") (pinfunction "GND_H19") (pintype "power_in"))
      (node (ref "U1") (pin "H2") (pinfunction "GND_H2") (pintype "power_in"))
      (node (ref "U1") (pin "H20") (pinfunction "GND_H20") (pintype "power_in"))
      (node (ref "U1") (pin "H3") (pinfunction "GND_H3") (pintype "power_in"))
      (node (ref "U1") (pin "H4") (pinfunction "GND_H4") (pintype "power_in"))
      (node (ref "U1") (pin "N1") (pinfunction "GND_N1") (pintype "power_in"))
      (node (ref "U1") (pin "N17") (pinfunction "GND_N17") (pintype "power_in"))
      (node (ref "U1") (pin "N18") (pinfunction "GND_N18") (pintype "power_in"))
      (node (ref "U1") (pin "N19") (pinfunction "GND_N19") (pintype "power_in"))
      (node (ref "U1") (pin "N2") (pinfunction "GND_N2") (pintype "power_in"))
      (node (ref "U1") (pin "N20") (pinfunction "GND_N20") (pintype "power_in"))
      (node (ref "U1") (pin "N3") (pinfunction "GND_N3") (pintype "power_in"))
      (node (ref "U1") (pin "N4") (pinfunction "GND_N4") (pintype "power_in"))
      (node (ref "U1") (pin "U13") (pinfunction "GND_U13") (pintype "power_in"))
      (node (ref "U1") (pin "U8") (pinfunction "GND_U8") (pintype "power_in"))
      (node (ref "U1") (pin "V13") (pinfunction "GND_V13") (pintype "power_in"))
      (node (ref "U1") (pin "V8") (pinfunction "GND_V8") (pintype "power_in"))
      (node (ref "U1") (pin "W13") (pinfunction "GND_W13") (pintype "power_in"))
      (node (ref "U1") (pin "W8") (pinfunction "GND_W8") (pintype "power_in"))
      (node (ref "U1") (pin "Y13") (pinfunction "GND_Y13") (pintype "power_in"))
      (node (ref "U1") (pin "Y8") (pinfunction "GND_Y8") (pintype "power_in"))
    )
    (net (code "209") (name "Net-(U1A-TXCLKOA)") (class "Default")
      (node (ref "R201") (pin "2") (pintype "passive"))
      (node (ref "U1") (pin "V12") (pinfunction "TXCLKOA_V12") (pintype "output"))
    )
    (net (code "210") (name "Net-(U1B-TXCLKOB)") (class "Default")
      (node (ref "R202") (pin "2") (pintype "passive"))
      (node (ref "U1") (pin "F19") (pinfunction "TXCLKOB_F19") (pintype "output"))
    )
    (net (code "211") (name "Net-(U1C-TXCLKOC)") (class "Default")
      (node (ref "R203") (pin "2") (pintype "passive"))
      (node (ref "U1") (pin "R2") (pinfunction "TXCLKOC_R2") (pintype "output"))
    )
    (net (code "212") (name "Net-(U1D-TXCLKOD)") (class "Default")
      (node (ref "R204") (pin "2") (pintype "passive"))
      (node (ref "U1") (pin "Y9") (pinfunction "TXCLKOD_Y9") (pintype "output"))
    )
    (net (code "213") (name "Net-(U1E-RXCLKA+)") (class "Default")
      (node (ref "R205") (pin "1") (pintype "passive"))
      (node (ref "U1") (pin "W11") (pinfunction "RXCLKA+_W11") (pintype "output"))
    )
    (net (code "214") (name "Net-(U1E-RXCLKA-)") (class "Default")
      (node (ref "R206") (pin "1") (pintype "passive"))
      (node (ref "U1") (pin "Y12") (pinfunction "RXCLKA-_Y12") (pintype "output"))
    )
    (net (code "215") (name "Net-(U1F-RXCLKB+)") (class "Default")
      (node (ref "R207") (pin "1") (pintype "passive"))
      (node (ref "U1") (pin "L18") (pinfunction "RXCLKB+_L18") (pintype "output"))
    )
    (net (code "216") (name "Net-(U1F-RXCLKB-)") (class "Default")
      (node (ref "R208") (pin "1") (pintype "passive"))
      (node (ref "U1") (pin "L19") (pinfunction "RXCLKB-_L19") (pintype "output"))
    )
    (net (code "217") (name "Net-(U1G-RXCLKC+)") (class "Default")
      (node (ref "R209") (pin "1") (pintype "passive"))
      (node (ref "U1") (pin "R3") (pinfunction "RXCLKC+_R3") (pintype "output"))
    )
    (net (code "218") (name "Net-(U1G-RXCLKC-)") (class "Default")
      (node (ref "R210") (pin "1") (pintype "passive"))
      (node (ref "U1") (pin "R4") (pinfunction "RXCLKC-_R4") (pintype "output"))
    )
    (net (code "219") (name "Net-(U1H-RXCLKD+)") (class "Default")
      (node (ref "R211") (pin "1") (pintype "passive"))
      (node (ref "U1") (pin "Y4") (pinfunction "RXCLKD+_Y4") (pintype "output"))
    )
    (net (code "220") (name "Net-(U1H-RXCLKD-)") (class "Default")
      (node (ref "R212") (pin "1") (pintype "passive"))
      (node (ref "U1") (pin "W4") (pinfunction "RXCLKD-_W4") (pintype "output"))
    )
  )
)
